# Temperature_sensor.net
KiCad netlist of a schematic drawn in EAGLE
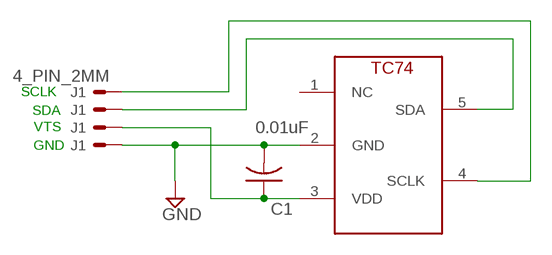
[diagram p0: schematic, sheet 1]

(export (version "E")
  (design (tool "Eeschema 10.0.6"))
  (components
    (comp (ref "C1")
      (value "0.01uF")
      (footprint "eagle-import:C0805")
      (libsource (lib "eagle-import") (part "C-USC0805"))
    )
    (comp (ref "J1")
      (value "4_PIN_2MM")
      (footprint "eagle-import:2MM_4PIN_LARGE")
      (libsource (lib "eagle-import") (part "4_PIN_2MM"))
    )
    (comp (ref "S1")
      (value "TC74")
      (footprint "eagle-import:SOT23-5L")
      (libsource (lib "eagle-import") (part "TC74"))
    )
  )
  (nets
    (net (code "1") (name "GND") (class "Default")
      (node (ref "C1") (pin "2") (pinfunction "2_2") (pintype "passive"))
      (node (ref "J1") (pin "8") (pinfunction "S3_8") (pintype "passive"))
      (node (ref "S1") (pin "2") (pinfunction "GND_2") (pintype "bidirectional"))
    )
    (net (code "2") (name "Net-(J1-S)") (class "Default")
      (node (ref "J1") (pin "2") (pinfunction "S_2") (pintype "passive"))
      (node (ref "S1") (pin "4") (pinfunction "SCLK_4") (pintype "bidirectional"))
    )
    (net (code "3") (name "Net-(J1-S1)") (class "Default")
      (node (ref "J1") (pin "4") (pinfunction "S1_4") (pintype "passive"))
      (node (ref "S1") (pin "5") (pinfunction "SDA_5") (pintype "bidirectional"))
    )
    (net (code "4") (name "Net-(J1-S2)") (class "Default")
      (node (ref "C1") (pin "1") (pinfunction "1_1") (pintype "passive"))
      (node (ref "J1") (pin "6") (pinfunction "S2_6") (pintype "passive"))
      (node (ref "S1") (pin "3") (pinfunction "VDD_3") (pintype "bidirectional"))
    )
    (net (code "5") (name "unconnected-(S1-NC-Pad1)") (class "Default")
      (node (ref "S1") (pin "1") (pinfunction "NC_1") (pintype "bidirectional"))
    )
  )
)
